# Nano_ELRS_2_4GHz_RX.net
KiCad netlist of a schematic drawn in EAGLE
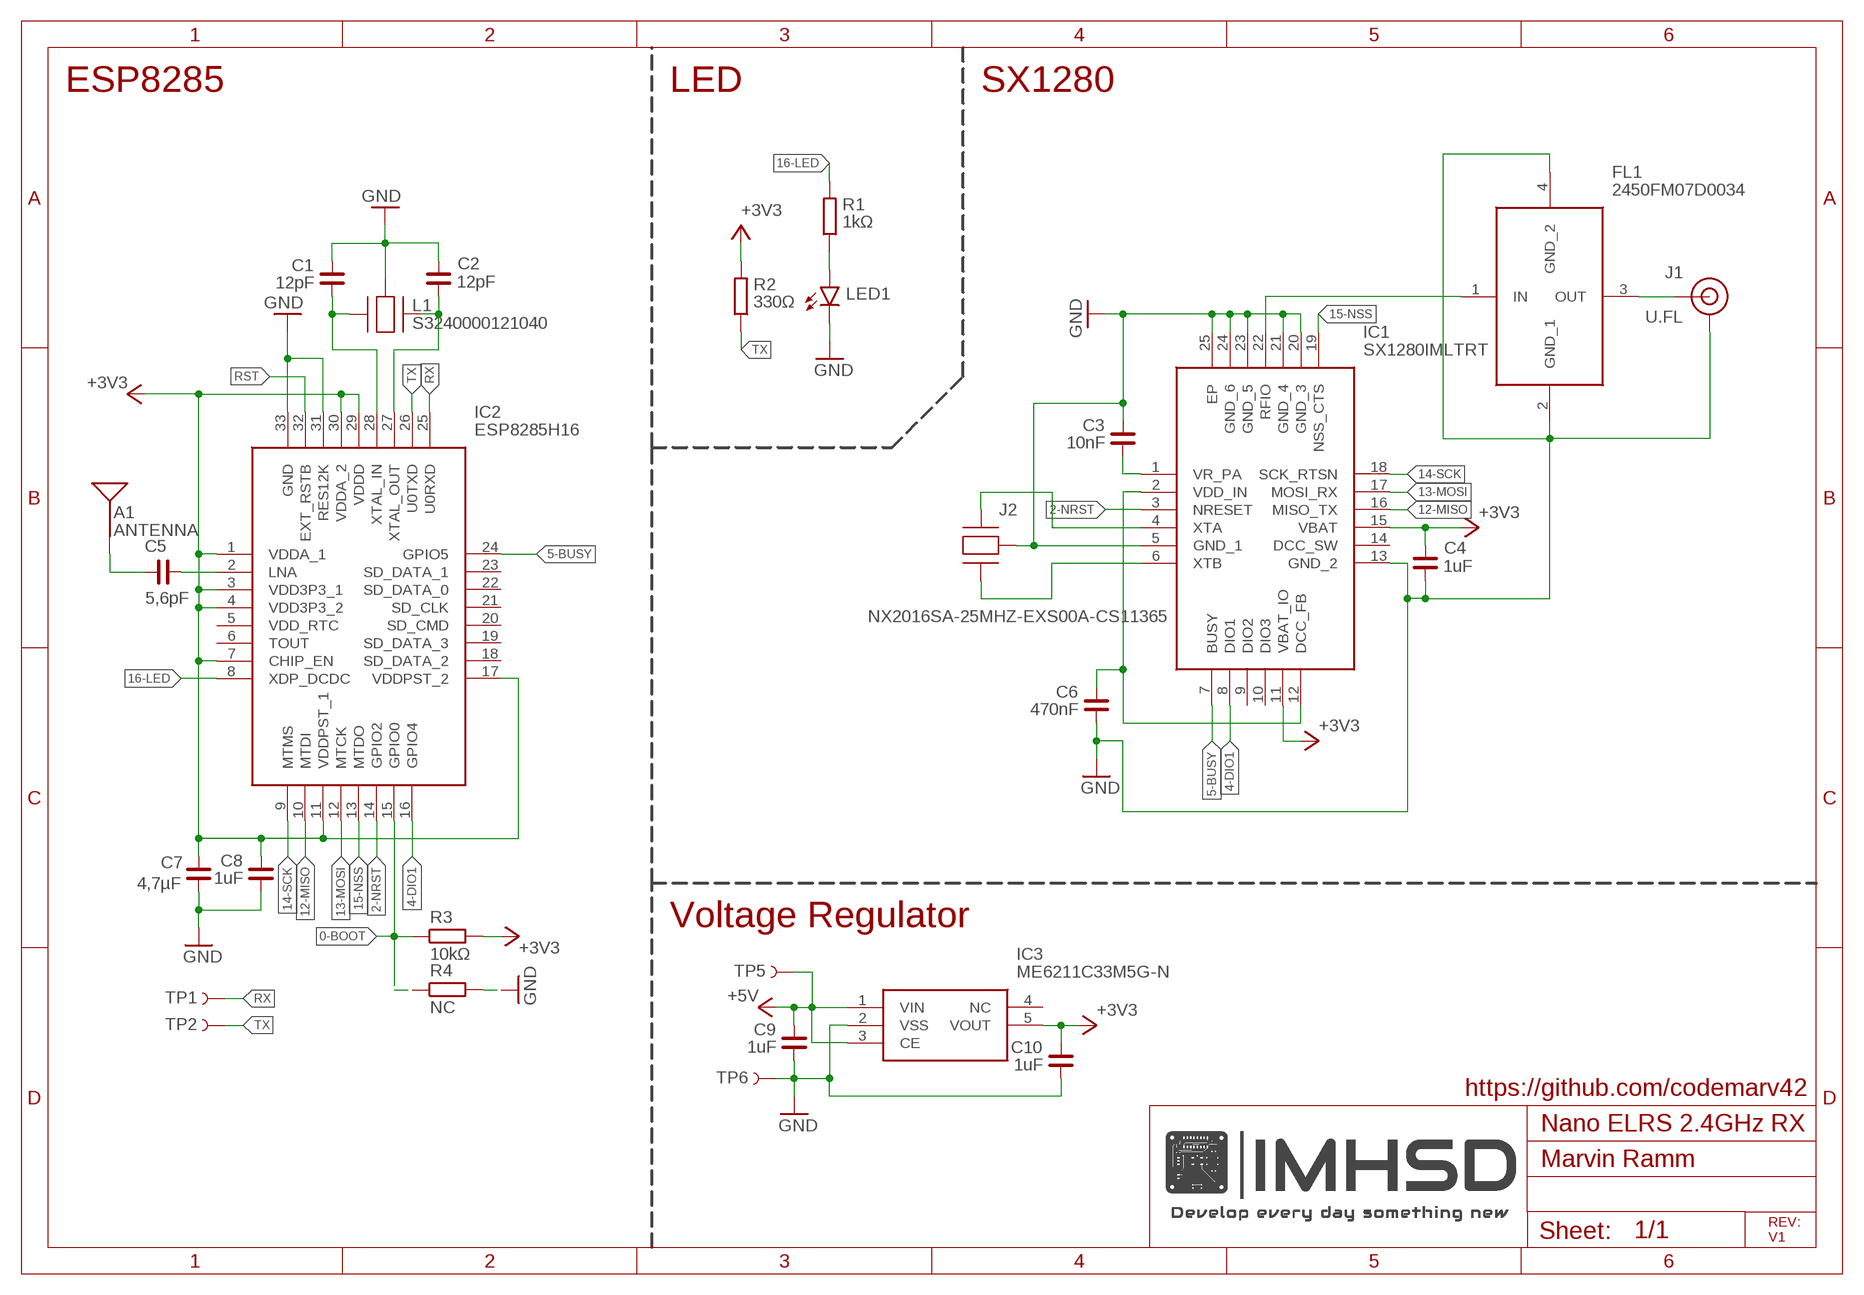
[diagram p0: schematic, sheet 1]

(export (version "E")
  (design (tool "Eeschema 10.0.6"))
  (components
    (comp (ref "A1")
      (value "ANTENNA")
      (footprint "eagle-import:TRACE_ANTENNA_2.4GHZ_NANO")
      (libsource (lib "eagle-import") (part "ANTENNA"))
    )
    (comp (ref "C1")
      (value "12pF")
      (footprint "eagle-import:C0402")
      (libsource (lib "eagle-import") (part "C_0402"))
    )
    (comp (ref "C2")
      (value "12pF")
      (footprint "eagle-import:C0402")
      (libsource (lib "eagle-import") (part "C_0402"))
    )
    (comp (ref "C3")
      (value "10nF")
      (footprint "eagle-import:C0402")
      (libsource (lib "eagle-import") (part "C_0402"))
    )
    (comp (ref "C4")
      (value "1uF")
      (footprint "eagle-import:C0402")
      (libsource (lib "eagle-import") (part "C_0402"))
    )
    (comp (ref "C5")
      (value "5,6pF")
      (footprint "eagle-import:C0402")
      (libsource (lib "eagle-import") (part "C_0402"))
    )
    (comp (ref "C6")
      (value "470nF")
      (footprint "eagle-import:C0402")
      (libsource (lib "eagle-import") (part "C_0402"))
    )
    (comp (ref "C7")
      (value "4,7µF")
      (footprint "eagle-import:C0603")
      (libsource (lib "eagle-import") (part "C_0603"))
    )
    (comp (ref "C8")
      (value "1uF")
      (footprint "eagle-import:C0402")
      (libsource (lib "eagle-import") (part "C_0402"))
    )
    (comp (ref "C9")
      (value "1uF")
      (footprint "eagle-import:C0402")
      (libsource (lib "eagle-import") (part "C_0402"))
    )
    (comp (ref "C10")
      (value "1uF")
      (footprint "eagle-import:C0402")
      (libsource (lib "eagle-import") (part "C_0402"))
    )
    (comp (ref "FL1")
      (value "2450FM07D0034")
      (footprint "eagle-import:2450FM07D0034")
      (libsource (lib "eagle-import") (part "2450FM07D0034"))
    )
    (comp (ref "IC1")
      (value "SX1280IMLTRT")
      (footprint "eagle-import:QFN50P400X400X100-25N")
      (fields (field (name "MOUSER_PART_NUMBER") "947-SX1280IMLTRT"))
      (libsource (lib "eagle-import") (part "SX1280IMLTRT"))
    )
    (comp (ref "IC2")
      (value "ESP8285H16")
      (footprint "eagle-import:QFN50P500X500X90-33N")
      (fields (field (name "MOUSER_PART_NUMBER") "356-ESP8285H16"))
      (libsource (lib "eagle-import") (part "ESP8285H16"))
    )
    (comp (ref "IC3")
      (value "ME6211C33M5G-N")
      (footprint "eagle-import:SOT95P270X145-5N")
      (libsource (lib "eagle-import") (part "ME6211C33M5G-N"))
    )
    (comp (ref "J1")
      (value "U.FL")
      (footprint "eagle-import:U.FL")
      (libsource (lib "eagle-import") (part "U.FL2PIN"))
    )
    (comp (ref "J2")
      (value "NX2016SA-25MHZ-EXS00A-CS11365")
      (footprint "eagle-import:NX2016SA25MHZEXS00ACS11365")
      (libsource (lib "eagle-import") (part "NX2016SA-25MHZ-EXS00A-CS11365"))
    )
    (comp (ref "L1")
      (value "SMD-3225_4P16MHZ_20PF_10PPM_-4")
      (footprint "eagle-import:SMD3225_4P16MHZ20PF10PPM4085")
      (fields (field (name "MANUFACTURER_PART_NUMBER") "SMD-3225_4P16MHZ 20PF 10PPM -40~+85℃"))
      (libsource (lib "eagle-import") (part "SMD-3225_4P16MHZ_20PF_10PPM_-4"))
    )
    (comp (ref "LED1")
      (value "SZYY0603W")
      (footprint "eagle-import:CHIP-LED0603")
      (libsource (lib "eagle-import") (part "LEDCHIP-LED0603"))
    )
    (comp (ref "R1")
      (value "1kΩ")
      (footprint "eagle-import:R0402")
      (libsource (lib "eagle-import") (part "R_0402"))
    )
    (comp (ref "R2")
      (value "330Ω")
      (footprint "eagle-import:R0402")
      (libsource (lib "eagle-import") (part "R_0402"))
    )
    (comp (ref "R3")
      (value "10kΩ")
      (footprint "eagle-import:R0402")
      (libsource (lib "eagle-import") (part "R_0402"))
    )
    (comp (ref "R4")
      (value "NC")
      (footprint "eagle-import:R0402")
      (libsource (lib "eagle-import") (part "R_0402"))
    )
    (comp (ref "TP1")
      (value "TEST-POINT3X5")
      (footprint "eagle-import:PAD.03X.05")
      (libsource (lib "eagle-import") (part "TEST-POINT3X5"))
    )
    (comp (ref "TP2")
      (value "TEST-POINT3X5")
      (footprint "eagle-import:PAD.03X.05")
      (libsource (lib "eagle-import") (part "TEST-POINT3X5"))
    )
    (comp (ref "TP5")
      (value "TEST-POINT3X5")
      (footprint "eagle-import:PAD.03X.05")
      (libsource (lib "eagle-import") (part "TEST-POINT3X5"))
    )
    (comp (ref "TP6")
      (value "TEST-POINT3X5")
      (footprint "eagle-import:PAD.03X.05")
      (libsource (lib "eagle-import") (part "TEST-POINT3X5"))
    )
  )
  (nets
    (net (code "1") (name "+3V3") (class "Default")
      (node (ref "C10") (pin "1") (pinfunction "1_1") (pintype "passive"))
      (node (ref "C4") (pin "1") (pinfunction "1_1") (pintype "passive"))
      (node (ref "C7") (pin "1") (pinfunction "1_1") (pintype "passive"))
      (node (ref "C8") (pin "1") (pinfunction "1_1") (pintype "passive"))
      (node (ref "IC1") (pin "11") (pinfunction "VBAT_IO_11") (pintype "bidirectional"))
      (node (ref "IC1") (pin "15") (pinfunction "VBAT_15") (pintype "bidirectional"))
      (node (ref "IC2") (pin "1") (pinfunction "VDDA_1_1") (pintype "bidirectional"))
      (node (ref "IC2") (pin "11") (pinfunction "VDDPST_1_11") (pintype "bidirectional"))
      (node (ref "IC2") (pin "17") (pinfunction "VDDPST_2_17") (pintype "bidirectional"))
      (node (ref "IC2") (pin "29") (pinfunction "VDDD_29") (pintype "bidirectional"))
      (node (ref "IC2") (pin "3") (pinfunction "VDD3P3_1_3") (pintype "bidirectional"))
      (node (ref "IC2") (pin "30") (pinfunction "VDDA_2_30") (pintype "bidirectional"))
      (node (ref "IC2") (pin "4") (pinfunction "VDD3P3_2_4") (pintype "bidirectional"))
      (node (ref "IC2") (pin "7") (pinfunction "CHIP_EN_7") (pintype "bidirectional"))
      (node (ref "IC3") (pin "5") (pinfunction "VOUT_5") (pintype "bidirectional"))
      (node (ref "R2") (pin "1") (pinfunction "1_1") (pintype "passive"))
      (node (ref "R3") (pin "1") (pinfunction "1_1") (pintype "passive"))
    )
    (net (code "2") (name "+5V") (class "Default")
      (node (ref "C9") (pin "1") (pinfunction "1_1") (pintype "passive"))
      (node (ref "IC3") (pin "1") (pinfunction "VIN_1") (pintype "bidirectional"))
      (node (ref "IC3") (pin "3") (pinfunction "CE_3") (pintype "bidirectional"))
      (node (ref "TP5") (pin "1") (pinfunction "1_1") (pintype "bidirectional"))
    )
    (net (code "3") (name "0-BOOT") (class "Default")
      (node (ref "IC2") (pin "15") (pinfunction "GPIO0_15") (pintype "bidirectional"))
      (node (ref "R3") (pin "2") (pinfunction "2_2") (pintype "passive"))
      (node (ref "R4") (pin "2") (pinfunction "2_2") (pintype "passive"))
    )
    (net (code "4") (name "2-NRST") (class "Default")
      (node (ref "IC1") (pin "3") (pinfunction "NRESET_3") (pintype "bidirectional"))
      (node (ref "IC2") (pin "14") (pinfunction "GPIO2_14") (pintype "bidirectional"))
    )
    (net (code "5") (name "4-DIO1") (class "Default")
      (node (ref "IC1") (pin "8") (pinfunction "DIO1_8") (pintype "bidirectional"))
      (node (ref "IC2") (pin "16") (pinfunction "GPIO4_16") (pintype "bidirectional"))
    )
    (net (code "6") (name "5-BUSY") (class "Default")
      (node (ref "IC1") (pin "7") (pinfunction "BUSY_7") (pintype "bidirectional"))
      (node (ref "IC2") (pin "24") (pinfunction "GPIO5_24") (pintype "bidirectional"))
    )
    (net (code "7") (name "12-MISO") (class "Default")
      (node (ref "IC1") (pin "16") (pinfunction "MISO_TX_16") (pintype "bidirectional"))
      (node (ref "IC2") (pin "10") (pinfunction "MTDI_10") (pintype "bidirectional"))
    )
    (net (code "8") (name "13-MOSI") (class "Default")
      (node (ref "IC1") (pin "17") (pinfunction "MOSI_RX_17") (pintype "bidirectional"))
      (node (ref "IC2") (pin "12") (pinfunction "MTCK_12") (pintype "bidirectional"))
    )
    (net (code "9") (name "14-SCK") (class "Default")
      (node (ref "IC1") (pin "18") (pinfunction "SCK_RTSN_18") (pintype "bidirectional"))
      (node (ref "IC2") (pin "9") (pinfunction "MTMS_9") (pintype "bidirectional"))
    )
    (net (code "10") (name "15-NSS") (class "Default")
      (node (ref "IC1") (pin "19") (pinfunction "NSS_CTS_19") (pintype "bidirectional"))
      (node (ref "IC2") (pin "13") (pinfunction "MTDO_13") (pintype "bidirectional"))
    )
    (net (code "11") (name "16-LED") (class "Default")
      (node (ref "IC2") (pin "8") (pinfunction "XDP_DCDC_8") (pintype "bidirectional"))
      (node (ref "R1") (pin "1") (pinfunction "1_1") (pintype "passive"))
    )
    (net (code "12") (name "GND") (class "Default")
      (node (ref "C1") (pin "1") (pinfunction "1_1") (pintype "passive"))
      (node (ref "C10") (pin "2") (pinfunction "2_2") (pintype "passive"))
      (node (ref "C2") (pin "1") (pinfunction "1_1") (pintype "passive"))
      (node (ref "C3") (pin "1") (pinfunction "1_1") (pintype "passive"))
      (node (ref "C4") (pin "2") (pinfunction "2_2") (pintype "passive"))
      (node (ref "C6") (pin "2") (pinfunction "2_2") (pintype "passive"))
      (node (ref "C7") (pin "2") (pinfunction "2_2") (pintype "passive"))
      (node (ref "C8") (pin "2") (pinfunction "2_2") (pintype "passive"))
      (node (ref "C9") (pin "2") (pinfunction "2_2") (pintype "passive"))
      (node (ref "FL1") (pin "2") (pinfunction "GND_1_2") (pintype "bidirectional"))
      (node (ref "FL1") (pin "4") (pinfunction "GND_2_4") (pintype "bidirectional"))
      (node (ref "IC1") (pin "13") (pinfunction "GND_2_13") (pintype "bidirectional"))
      (node (ref "IC1") (pin "20") (pinfunction "GND_3_20") (pintype "bidirectional"))
      (node (ref "IC1") (pin "21") (pinfunction "GND_4_21") (pintype "bidirectional"))
      (node (ref "IC1") (pin "23") (pinfunction "GND_5_23") (pintype "bidirectional"))
      (node (ref "IC1") (pin "24") (pinfunction "GND_6_24") (pintype "bidirectional"))
      (node (ref "IC1") (pin "25") (pinfunction "EP_25") (pintype "bidirectional"))
      (node (ref "IC1") (pin "5") (pinfunction "GND_1_5") (pintype "bidirectional"))
      (node (ref "IC2") (pin "31") (pinfunction "RES12K_31") (pintype "bidirectional"))
      (node (ref "IC2") (pin "33") (pinfunction "GND_33") (pintype "bidirectional"))
      (node (ref "IC3") (pin "2") (pinfunction "VSS_2") (pintype "bidirectional"))
      (node (ref "J1") (pin "1") (pinfunction "GND_1") (pintype "bidirectional"))
      (node (ref "J1") (pin "2") (pinfunction "GND_2") (pintype "bidirectional"))
      (node (ref "J2") (pin "2") (pinfunction "GND_2_2") (pintype "bidirectional"))
      (node (ref "J2") (pin "4") (pinfunction "GND_2_4") (pintype "bidirectional"))
      (node (ref "L1") (pin "2") (pinfunction "GND_2_2") (pintype "bidirectional"))
      (node (ref "L1") (pin "4") (pinfunction "GND_2_4") (pintype "bidirectional"))
      (node (ref "LED1") (pin "C") (pinfunction "C_C") (pintype "passive"))
      (node (ref "R4") (pin "1") (pinfunction "1_1") (pintype "passive"))
      (node (ref "TP6") (pin "1") (pinfunction "1_1") (pintype "bidirectional"))
    )
    (net (code "13") (name "Net-(A1-SIGNAL)") (class "Default")
      (node (ref "A1") (pin "ANT") (pinfunction "SIGNAL_ANT") (pintype "bidirectional"))
      (node (ref "C5") (pin "2") (pinfunction "2_2") (pintype "passive"))
    )
    (net (code "14") (name "Net-(FL1-IN)") (class "Default")
      (node (ref "FL1") (pin "1") (pinfunction "IN_1") (pintype "bidirectional"))
      (node (ref "IC1") (pin "22") (pinfunction "RFIO_22") (pintype "bidirectional"))
    )
    (net (code "15") (name "Net-(FL1-OUT)") (class "Default")
      (node (ref "FL1") (pin "3") (pinfunction "OUT_3") (pintype "bidirectional"))
      (node (ref "J1") (pin "FEED") (pinfunction "SIGNAL_FEED") (pintype "bidirectional"))
    )
    (net (code "16") (name "Net-(IC1-DCC_FB)") (class "Default")
      (node (ref "C6") (pin "1") (pinfunction "1_1") (pintype "passive"))
      (node (ref "IC1") (pin "12") (pinfunction "DCC_FB_12") (pintype "bidirectional"))
      (node (ref "IC1") (pin "2") (pinfunction "VDD_IN_2") (pintype "bidirectional"))
    )
    (net (code "17") (name "Net-(IC1-VR_PA)") (class "Default")
      (node (ref "C3") (pin "2") (pinfunction "2_2") (pintype "passive"))
      (node (ref "IC1") (pin "1") (pinfunction "VR_PA_1") (pintype "bidirectional"))
    )
    (net (code "18") (name "Net-(IC1-XTA)") (class "Default")
      (node (ref "IC1") (pin "4") (pinfunction "XTA_4") (pintype "bidirectional"))
      (node (ref "J2") (pin "1") (pinfunction "CRYSTAL_1_1") (pintype "bidirectional"))
    )
    (net (code "19") (name "Net-(IC1-XTB)") (class "Default")
      (node (ref "IC1") (pin "6") (pinfunction "XTB_6") (pintype "bidirectional"))
      (node (ref "J2") (pin "3") (pinfunction "CRYSTAL_2_3") (pintype "bidirectional"))
    )
    (net (code "20") (name "Net-(IC2-LNA)") (class "Default")
      (node (ref "C5") (pin "1") (pinfunction "1_1") (pintype "passive"))
      (node (ref "IC2") (pin "2") (pinfunction "LNA_2") (pintype "bidirectional"))
    )
    (net (code "21") (name "Net-(IC2-XTAL_IN)") (class "Default")
      (node (ref "C1") (pin "2") (pinfunction "2_2") (pintype "passive"))
      (node (ref "IC2") (pin "28") (pinfunction "XTAL_IN_28") (pintype "bidirectional"))
      (node (ref "L1") (pin "1") (pinfunction "CRYSTAL_1_1") (pintype "bidirectional"))
    )
    (net (code "22") (name "Net-(IC2-XTAL_OUT)") (class "Default")
      (node (ref "C2") (pin "2") (pinfunction "2_2") (pintype "passive"))
      (node (ref "IC2") (pin "27") (pinfunction "XTAL_OUT_27") (pintype "bidirectional"))
      (node (ref "L1") (pin "3") (pinfunction "CRYSTAL_2_3") (pintype "bidirectional"))
    )
    (net (code "23") (name "Net-(LED1-PadA)") (class "Default")
      (node (ref "LED1") (pin "A") (pinfunction "A_A") (pintype "passive"))
      (node (ref "R1") (pin "2") (pinfunction "2_2") (pintype "passive"))
    )
    (net (code "24") (name "RST") (class "Default")
      (node (ref "IC2") (pin "32") (pinfunction "EXT_RSTB_32") (pintype "bidirectional"))
    )
    (net (code "25") (name "RX") (class "Default")
      (node (ref "IC2") (pin "25") (pinfunction "U0RXD_25") (pintype "bidirectional"))
      (node (ref "TP1") (pin "1") (pinfunction "1_1") (pintype "bidirectional"))
    )
    (net (code "26") (name "TX") (class "Default")
      (node (ref "IC2") (pin "26") (pinfunction "U0TXD_26") (pintype "bidirectional"))
      (node (ref "R2") (pin "2") (pinfunction "2_2") (pintype "passive"))
      (node (ref "TP2") (pin "1") (pinfunction "1_1") (pintype "bidirectional"))
    )
    (net (code "27") (name "unconnected-(IC1-DCC_SW-Pad14)") (class "Default")
      (node (ref "IC1") (pin "14") (pinfunction "DCC_SW_14") (pintype "bidirectional"))
    )
    (net (code "28") (name "unconnected-(IC1-DIO2-Pad9)") (class "Default")
      (node (ref "IC1") (pin "9") (pinfunction "DIO2_9") (pintype "bidirectional"))
    )
    (net (code "29") (name "unconnected-(IC1-DIO3-Pad10)") (class "Default")
      (node (ref "IC1") (pin "10") (pinfunction "DIO3_10") (pintype "bidirectional"))
    )
    (net (code "30") (name "unconnected-(IC2-SD_CLK-Pad21)") (class "Default")
      (node (ref "IC2") (pin "21") (pinfunction "SD_CLK_21") (pintype "bidirectional"))
    )
    (net (code "31") (name "unconnected-(IC2-SD_CMD-Pad20)") (class "Default")
      (node (ref "IC2") (pin "20") (pinfunction "SD_CMD_20") (pintype "bidirectional"))
    )
    (net (code "32") (name "unconnected-(IC2-SD_DATA_0-Pad22)") (class "Default")
      (node (ref "IC2") (pin "22") (pinfunction "SD_DATA_0_22") (pintype "bidirectional"))
    )
    (net (code "33") (name "unconnected-(IC2-SD_DATA_1-Pad23)") (class "Default")
      (node (ref "IC2") (pin "23") (pinfunction "SD_DATA_1_23") (pintype "bidirectional"))
    )
    (net (code "34") (name "unconnected-(IC2-SD_DATA_2-Pad18)") (class "Default")
      (node (ref "IC2") (pin "18") (pinfunction "SD_DATA_2_18") (pintype "bidirectional"))
    )
    (net (code "35") (name "unconnected-(IC2-SD_DATA_3-Pad19)") (class "Default")
      (node (ref "IC2") (pin "19") (pinfunction "SD_DATA_3_19") (pintype "bidirectional"))
    )
    (net (code "36") (name "unconnected-(IC2-TOUT-Pad6)") (class "Default")
      (node (ref "IC2") (pin "6") (pinfunction "TOUT_6") (pintype "bidirectional"))
    )
    (net (code "37") (name "unconnected-(IC2-VDD_RTC-Pad5)") (class "Default")
      (node (ref "IC2") (pin "5") (pinfunction "VDD_RTC_5") (pintype "bidirectional"))
    )
    (net (code "38") (name "unconnected-(IC3-NC-Pad4)") (class "Default")
      (node (ref "IC3") (pin "4") (pinfunction "NC_4") (pintype "no_connect"))
    )
  )
)
